# Vertigo_Core.net
KiCad netlist of a schematic drawn in Altium Designer
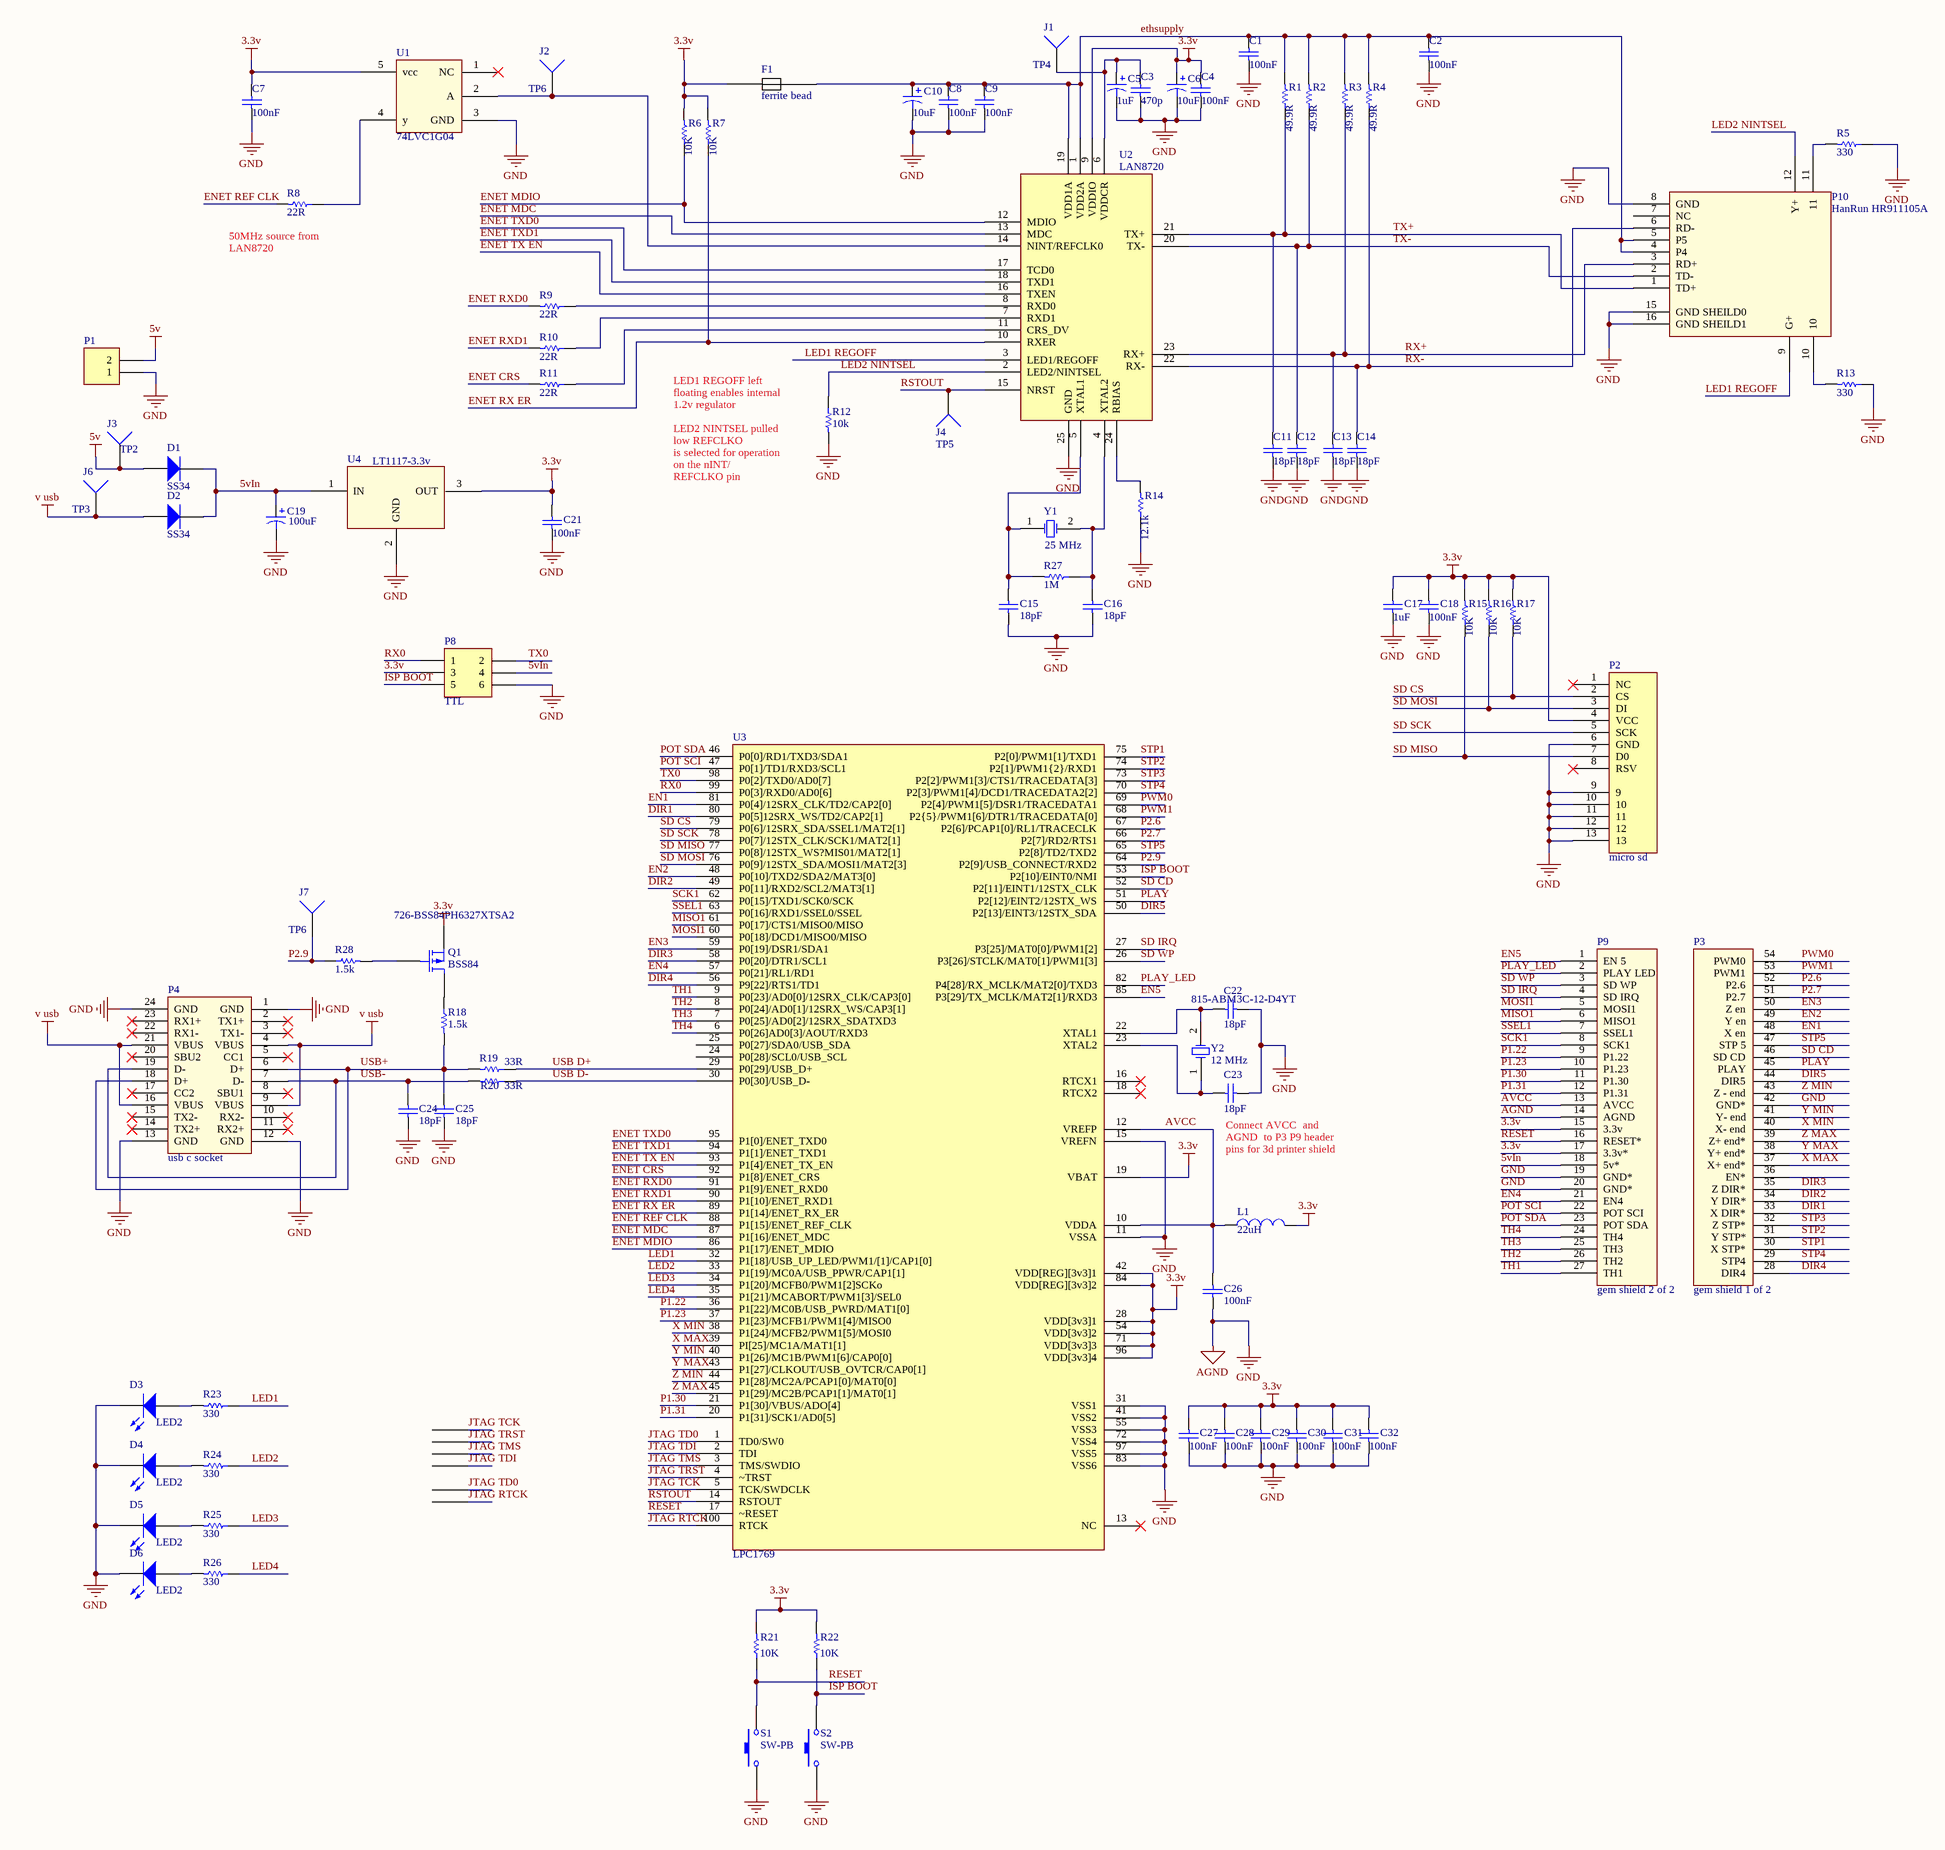
[diagram p0: Vertigo Core.SchDoc]

(export (version "E")
  (design (tool "Eeschema 10.0.6"))
  (components
    (comp (ref "C1")
      (value "100nF")
      (footprint "0805")
      (description "Capacitor (Semiconductor SIM Model)")
      (fields (field (name "PUBLISHER") "Altium Limited"))
      (libsource (lib "Miscellaneous Devices") (part "Cap Semi"))
    )
    (comp (ref "C2")
      (value "100nF")
      (footprint "0805")
      (description "Capacitor (Semiconductor SIM Model)")
      (fields (field (name "PUBLISHER") "Altium Limited"))
      (libsource (lib "Miscellaneous Devices") (part "Cap Semi"))
    )
    (comp (ref "C3")
      (value "470p")
      (footprint "0805")
      (description "Capacitor (Semiconductor SIM Model)")
      (fields (field (name "Comment") "470pF") (field (name "PUBLISHER") "Altium Limited"))
      (libsource (lib "Miscellaneous Devices") (part "Cap Semi"))
    )
    (comp (ref "C4")
      (value "100nF")
      (footprint "0805")
      (description "Capacitor (Semiconductor SIM Model)")
      (fields (field (name "PUBLISHER") "Altium Limited"))
      (libsource (lib "Miscellaneous Devices") (part "Cap Semi"))
    )
    (comp (ref "C5")
      (value "1uF")
      (footprint "0805")
      (description "Polarized Capacitor (Radial)")
      (fields (field (name "PUBLISHER") "Altium Limited"))
      (libsource (lib "Miscellaneous Devices") (part "Cap Pol1"))
    )
    (comp (ref "C6")
      (value "10uF")
      (footprint "0805")
      (description "Polarized Capacitor (Radial)")
      (fields (field (name "PUBLISHER") "Altium Limited"))
      (libsource (lib "Miscellaneous Devices") (part "Cap Pol1"))
    )
    (comp (ref "C7")
      (value "100nF")
      (footprint "0805")
      (description "Capacitor (Semiconductor SIM Model)")
      (fields (field (name "PUBLISHER") "Altium Limited"))
      (libsource (lib "Miscellaneous Devices") (part "Cap Semi"))
    )
    (comp (ref "C8")
      (value "100nF")
      (footprint "0805")
      (description "Capacitor (Semiconductor SIM Model)")
      (fields (field (name "PUBLISHER") "Altium Limited"))
      (libsource (lib "Miscellaneous Devices") (part "Cap Semi"))
    )
    (comp (ref "C9")
      (value "100nF")
      (footprint "0805")
      (description "Capacitor (Semiconductor SIM Model)")
      (fields (field (name "PUBLISHER") "Altium Limited"))
      (libsource (lib "Miscellaneous Devices") (part "Cap Semi"))
    )
    (comp (ref "C10")
      (value "10uF")
      (footprint "0805")
      (description "Polarized Capacitor (Radial)")
      (fields (field (name "PUBLISHER") "Altium Limited"))
      (libsource (lib "Miscellaneous Devices") (part "Cap Pol1"))
    )
    (comp (ref "C11")
      (value "18pF")
      (footprint "0805")
      (description "Capacitor (Semiconductor SIM Model)")
      (fields (field (name "Comment") "18pf") (field (name "PUBLISHER") "Altium Limited"))
      (libsource (lib "Miscellaneous Devices") (part "Cap Semi"))
    )
    (comp (ref "C12")
      (value "18pF")
      (footprint "0805")
      (description "Capacitor (Semiconductor SIM Model)")
      (fields (field (name "Comment") "18pf") (field (name "PUBLISHER") "Altium Limited"))
      (libsource (lib "Miscellaneous Devices") (part "Cap Semi"))
    )
    (comp (ref "C13")
      (value "18pF")
      (footprint "0805")
      (description "Capacitor (Semiconductor SIM Model)")
      (fields (field (name "Comment") "18pf") (field (name "PUBLISHER") "Altium Limited"))
      (libsource (lib "Miscellaneous Devices") (part "Cap Semi"))
    )
    (comp (ref "C14")
      (value "18pF")
      (footprint "0805")
      (description "Capacitor (Semiconductor SIM Model)")
      (fields (field (name "Comment") "18pf") (field (name "PUBLISHER") "Altium Limited"))
      (libsource (lib "Miscellaneous Devices") (part "Cap Semi"))
    )
    (comp (ref "C15")
      (value "18pF")
      (footprint "0805")
      (description "Capacitor (Semiconductor SIM Model)")
      (fields (field (name "PUBLISHER") "Altium Limited"))
      (libsource (lib "Miscellaneous Devices") (part "Cap Semi"))
    )
    (comp (ref "C16")
      (value "18pF")
      (footprint "0805")
      (description "Capacitor (Semiconductor SIM Model)")
      (fields (field (name "PUBLISHER") "Altium Limited"))
      (libsource (lib "Miscellaneous Devices") (part "Cap Semi"))
    )
    (comp (ref "C17")
      (value "1uF")
      (footprint "0805")
      (description "Capacitor (Semiconductor SIM Model)")
      (fields (field (name "PUBLISHER") "Altium Limited"))
      (libsource (lib "Miscellaneous Devices") (part "Cap Semi"))
    )
    (comp (ref "C18")
      (value "100nF")
      (footprint "0805")
      (description "Capacitor (Semiconductor SIM Model)")
      (fields (field (name "PUBLISHER") "Altium Limited"))
      (libsource (lib "Miscellaneous Devices") (part "Cap Semi"))
    )
    (comp (ref "C19")
      (value "100uF")
      (footprint "470uf/ 100uf 50v smd")
      (description "Polarized Capacitor (Radial)")
      (fields (field (name "Comment") "10uF") (field (name "PUBLISHER") "Altium Limited"))
      (libsource (lib "Miscellaneous Devices") (part "Cap Pol1"))
    )
    (comp (ref "C21")
      (value "100nF")
      (footprint "0805")
      (description "Capacitor (Semiconductor SIM Model)")
      (fields (field (name "PUBLISHER") "Altium Limited"))
      (libsource (lib "Miscellaneous Devices") (part "Cap Semi"))
    )
    (comp (ref "C22")
      (value "18pF")
      (footprint "0805")
      (description "Capacitor (Semiconductor SIM Model)")
      (fields (field (name "PUBLISHER") "Altium Limited"))
      (libsource (lib "Miscellaneous Devices") (part "Cap Semi"))
    )
    (comp (ref "C23")
      (value "18pF")
      (footprint "0805")
      (description "Capacitor (Semiconductor SIM Model)")
      (fields (field (name "PUBLISHER") "Altium Limited"))
      (libsource (lib "Miscellaneous Devices") (part "Cap Semi"))
    )
    (comp (ref "C24")
      (value "18pF")
      (footprint "0805")
      (description "Capacitor (Semiconductor SIM Model)")
      (fields (field (name "PUBLISHER") "Altium Limited"))
      (libsource (lib "Miscellaneous Devices") (part "Cap Semi"))
    )
    (comp (ref "C25")
      (value "18pF")
      (footprint "0805")
      (description "Capacitor (Semiconductor SIM Model)")
      (fields (field (name "PUBLISHER") "Altium Limited"))
      (libsource (lib "Miscellaneous Devices") (part "Cap Semi"))
    )
    (comp (ref "C26")
      (value "100nF")
      (footprint "0805")
      (description "Capacitor (Semiconductor SIM Model)")
      (fields (field (name "PUBLISHER") "Altium Limited"))
      (libsource (lib "Miscellaneous Devices") (part "Cap Semi"))
    )
    (comp (ref "C27")
      (value "100nF")
      (footprint "0805")
      (description "Capacitor (Semiconductor SIM Model)")
      (fields (field (name "PUBLISHER") "Altium Limited"))
      (libsource (lib "Miscellaneous Devices") (part "Cap Semi"))
    )
    (comp (ref "C28")
      (value "100nF")
      (footprint "0805")
      (description "Capacitor (Semiconductor SIM Model)")
      (fields (field (name "PUBLISHER") "Altium Limited"))
      (libsource (lib "Miscellaneous Devices") (part "Cap Semi"))
    )
    (comp (ref "C29")
      (value "100nF")
      (footprint "0805")
      (description "Capacitor (Semiconductor SIM Model)")
      (fields (field (name "PUBLISHER") "Altium Limited"))
      (libsource (lib "Miscellaneous Devices") (part "Cap Semi"))
    )
    (comp (ref "C30")
      (value "100nF")
      (footprint "0805")
      (description "Capacitor (Semiconductor SIM Model)")
      (fields (field (name "PUBLISHER") "Altium Limited"))
      (libsource (lib "Miscellaneous Devices") (part "Cap Semi"))
    )
    (comp (ref "C31")
      (value "100nF")
      (footprint "0805")
      (description "Capacitor (Semiconductor SIM Model)")
      (fields (field (name "PUBLISHER") "Altium Limited"))
      (libsource (lib "Miscellaneous Devices") (part "Cap Semi"))
    )
    (comp (ref "C32")
      (value "100nF")
      (footprint "0805")
      (description "Capacitor (Semiconductor SIM Model)")
      (fields (field (name "PUBLISHER") "Altium Limited"))
      (libsource (lib "Miscellaneous Devices") (part "Cap Semi"))
    )
    (comp (ref "D1")
      (value "SS34")
      (footprint "Diode")
      (description "High Conductance Fast Diode")
      (fields (field (name "PUBLISHER") "Altium Limited"))
      (libsource (lib "Miscellaneous Devices") (part "Diode 1N914"))
    )
    (comp (ref "D2")
      (value "SS34")
      (footprint "Diode")
      (description "High Conductance Fast Diode")
      (fields (field (name "PUBLISHER") "Altium Limited"))
      (libsource (lib "Miscellaneous Devices") (part "Diode 1N914"))
    )
    (comp (ref "D3")
      (value "LED2")
      (footprint "0805 LED")
      (description "Typical RED, GREEN, YELLOW, AMBER GaAs LED")
      (fields (field (name "PUBLISHER") "Altium Limited"))
      (libsource (lib "Miscellaneous Devices") (part "LED2"))
    )
    (comp (ref "D4")
      (value "LED2")
      (footprint "0805 LED")
      (description "Typical RED, GREEN, YELLOW, AMBER GaAs LED")
      (fields (field (name "PUBLISHER") "Altium Limited"))
      (libsource (lib "Miscellaneous Devices") (part "LED2"))
    )
    (comp (ref "D5")
      (value "LED2")
      (footprint "0805 LED")
      (description "Typical RED, GREEN, YELLOW, AMBER GaAs LED")
      (fields (field (name "PUBLISHER") "Altium Limited"))
      (libsource (lib "Miscellaneous Devices") (part "LED2"))
    )
    (comp (ref "D6")
      (value "LED2")
      (footprint "0805 LED")
      (description "Typical RED, GREEN, YELLOW, AMBER GaAs LED")
      (fields (field (name "PUBLISHER") "Altium Limited"))
      (libsource (lib "Miscellaneous Devices") (part "LED2"))
    )
    (comp (ref "F1")
      (value "ferrite bead")
      (footprint "0805")
      (libsource (lib "32 bit cnc") (part "ferrite bead"))
    )
    (comp (ref "J1")
      (value "TP4")
      (footprint "test point")
      (description "Socket")
      (fields (field (name "PUBLISHER") "Altium Limited"))
      (libsource (lib "Miscellaneous Connectors") (part "Socket"))
    )
    (comp (ref "J2")
      (value "TP6")
      (footprint "test point")
      (description "Socket")
      (fields (field (name "PUBLISHER") "Altium Limited"))
      (libsource (lib "Miscellaneous Connectors") (part "Socket"))
    )
    (comp (ref "J3")
      (value "TP2")
      (footprint "test point")
      (description "Socket")
      (fields (field (name "PUBLISHER") "Altium Limited"))
      (libsource (lib "Miscellaneous Connectors") (part "Socket"))
    )
    (comp (ref "J4")
      (value "TP5")
      (footprint "test point")
      (description "Socket")
      (fields (field (name "PUBLISHER") "Altium Limited"))
      (libsource (lib "Miscellaneous Connectors") (part "Socket"))
    )
    (comp (ref "J6")
      (value "TP3")
      (footprint "test point")
      (description "Socket")
      (fields (field (name "PUBLISHER") "Altium Limited"))
      (libsource (lib "Miscellaneous Connectors") (part "Socket"))
    )
    (comp (ref "J7")
      (value "TP6")
      (footprint "test point")
      (description "Socket")
      (fields (field (name "PUBLISHER") "Altium Limited"))
      (libsource (lib "Miscellaneous Connectors") (part "Socket"))
    )
    (comp (ref "L1")
      (value "22uH")
      (footprint "0805")
      (description "Inductor")
      (fields (field (name "PUBLISHER") "Altium Limited"))
      (libsource (lib "Miscellaneous Devices") (part "Inductor"))
    )
    (comp (ref "P1")
      (value "Header 2")
      (footprint "HDR1X2")
      (description "Header, 2-Pin")
      (fields (field (name "PUBLISHER") "Altium Limited"))
      (libsource (lib "Miscellaneous Connectors") (part "Header 2"))
    )
    (comp (ref "P2")
      (value "micro sd")
      (footprint "DM3 SD card")
      (libsource (lib "32 bit cnc") (part "micro sd"))
    )
    (comp (ref "P3")
      (value "gem shield 1 of 2")
      (footprint "gem shield 1 of 2")
      (libsource (lib "32 bit cnc") (part "gem shield 1 of 2"))
    )
    (comp (ref "P4")
      (value "usb c socket")
      (footprint "USB C type")
      (description "Mouser 538-105450-0101")
      (libsource (lib "32 bit cnc") (part "usb c socket"))
    )
    (comp (ref "P5") (value "JTAG2") (footprint "JTAG2") (libsource (lib "32 bit cnc") (part "JTAG2")))
    (comp (ref "P6") (value "JTAG") (footprint "JTAG") (libsource (lib "32 bit cnc") (part "JTAG")))
    (comp (ref "P8")
      (value "TTL")
      (footprint "HDR2X3")
      (description "Header, 3-Pin, Dual row")
      (fields (field (name "PUBLISHER") "Altium Limited"))
      (libsource (lib "Miscellaneous Connectors") (part "Header 3X2"))
    )
    (comp (ref "P9")
      (value "gem shield 2 of 2")
      (footprint "gem shield 2 of 2")
      (libsource (lib "32 bit cnc") (part "gem shield 2 of 2"))
    )
    (comp (ref "P10")
      (value "HanRun HR911105A")
      (footprint "Hanrun")
      (libsource (lib "32 bit cnc") (part "RJ45"))
    )
    (comp (ref "Q1")
      (value "BSS84")
      (footprint "SOT23")
      (description "P-Channel MOSFET")
      (fields
        (field (name "SUPPLIER PART NUMBER 1") "726-BSS84PH6327XTSA2")
        (field (name "PUBLISHER") "Altium Limited")
      )
      (libsource (lib "Miscellaneous Devices") (part "MOSFET-P"))
    )
    (comp (ref "R1")
      (value "49.9R")
      (footprint "0805")
      (description "Resistor")
      (fields (field (name "Comment") "49.9") (field (name "PUBLISHER") "Altium Limited"))
      (libsource (lib "Miscellaneous Devices") (part "Res1"))
    )
    (comp (ref "R2")
      (value "49.9R")
      (footprint "0805")
      (description "Resistor")
      (fields (field (name "Comment") "49.9") (field (name "PUBLISHER") "Altium Limited"))
      (libsource (lib "Miscellaneous Devices") (part "Res1"))
    )
    (comp (ref "R3")
      (value "49.9R")
      (footprint "0805")
      (description "Resistor")
      (fields (field (name "Comment") "49.9") (field (name "PUBLISHER") "Altium Limited"))
      (libsource (lib "Miscellaneous Devices") (part "Res1"))
    )
    (comp (ref "R4")
      (value "49.9R")
      (footprint "0805")
      (description "Resistor")
      (fields (field (name "Comment") "49.9") (field (name "PUBLISHER") "Altium Limited"))
      (libsource (lib "Miscellaneous Devices") (part "Res1"))
    )
    (comp (ref "R5")
      (value "330")
      (footprint "0805")
      (description "Resistor")
      (fields (field (name "PUBLISHER") "Altium Limited"))
      (libsource (lib "Miscellaneous Devices") (part "Res1"))
    )
    (comp (ref "R6")
      (value "10K")
      (footprint "0805")
      (description "Resistor")
      (fields (field (name "Comment") "10k") (field (name "PUBLISHER") "Altium Limited"))
      (libsource (lib "Miscellaneous Devices") (part "Res1"))
    )
    (comp (ref "R7")
      (value "10K")
      (footprint "0805")
      (description "Resistor")
      (fields (field (name "Comment") "10k") (field (name "PUBLISHER") "Altium Limited"))
      (libsource (lib "Miscellaneous Devices") (part "Res1"))
    )
    (comp (ref "R8")
      (value "22R")
      (footprint "0603")
      (description "Resistor")
      (fields (field (name "PUBLISHER") "Altium Limited"))
      (libsource (lib "Miscellaneous Devices") (part "Res1"))
    )
    (comp (ref "R9")
      (value "22R")
      (footprint "0603")
      (description "Resistor")
      (fields (field (name "PUBLISHER") "Altium Limited"))
      (libsource (lib "Miscellaneous Devices") (part "Res1"))
    )
    (comp (ref "R10")
      (value "22R")
      (footprint "0603")
      (description "Resistor")
      (fields (field (name "PUBLISHER") "Altium Limited"))
      (libsource (lib "Miscellaneous Devices") (part "Res1"))
    )
    (comp (ref "R11")
      (value "22R")
      (footprint "0603")
      (description "Resistor")
      (fields (field (name "PUBLISHER") "Altium Limited"))
      (libsource (lib "Miscellaneous Devices") (part "Res1"))
    )
    (comp (ref "R12")
      (value "10k")
      (footprint "0805")
      (description "Resistor")
      (fields (field (name "PUBLISHER") "Altium Limited"))
      (libsource (lib "Miscellaneous Devices") (part "Res1"))
    )
    (comp (ref "R13")
      (value "330")
      (footprint "0805")
      (description "Resistor")
      (fields (field (name "PUBLISHER") "Altium Limited"))
      (libsource (lib "Miscellaneous Devices") (part "Res1"))
    )
    (comp (ref "R14")
      (value "12.1k")
      (footprint "0805")
      (description "Resistor")
      (fields (field (name "PUBLISHER") "Altium Limited"))
      (libsource (lib "Miscellaneous Devices") (part "Res1"))
    )
    (comp (ref "R15")
      (value "10K")
      (footprint "0805")
      (description "Resistor")
      (fields (field (name "Comment") "10k") (field (name "PUBLISHER") "Altium Limited"))
      (libsource (lib "Miscellaneous Devices") (part "Res1"))
    )
    (comp (ref "R16")
      (value "10K")
      (footprint "0805")
      (description "Resistor")
      (fields (field (name "Comment") "10k") (field (name "PUBLISHER") "Altium Limited"))
      (libsource (lib "Miscellaneous Devices") (part "Res1"))
    )
    (comp (ref "R17")
      (value "10K")
      (footprint "0805")
      (description "Resistor")
      (fields (field (name "Comment") "10k") (field (name "PUBLISHER") "Altium Limited"))
      (libsource (lib "Miscellaneous Devices") (part "Res1"))
    )
    (comp (ref "R18")
      (value "1.5k")
      (footprint "0603")
      (description "Resistor")
      (fields (field (name "Comment") "1.5K") (field (name "PUBLISHER") "Altium Limited"))
      (libsource (lib "Miscellaneous Devices") (part "Res1"))
    )
    (comp (ref "R19")
      (value "33R")
      (footprint "0805")
      (description "Resistor")
      (fields (field (name "PUBLISHER") "Altium Limited"))
      (libsource (lib "Miscellaneous Devices") (part "Res1"))
    )
    (comp (ref "R20")
      (value "33R")
      (footprint "0805")
      (description "Resistor")
      (fields (field (name "PUBLISHER") "Altium Limited"))
      (libsource (lib "Miscellaneous Devices") (part "Res1"))
    )
    (comp (ref "R21")
      (value "10K")
      (footprint "0805")
      (description "Resistor")
      (fields (field (name "Comment") "10k") (field (name "PUBLISHER") "Altium Limited"))
      (libsource (lib "Miscellaneous Devices") (part "Res1"))
    )
    (comp (ref "R22")
      (value "10K")
      (footprint "0805")
      (description "Resistor")
      (fields (field (name "Comment") "10k") (field (name "PUBLISHER") "Altium Limited"))
      (libsource (lib "Miscellaneous Devices") (part "Res1"))
    )
    (comp (ref "R23")
      (value "330")
      (footprint "0805")
      (description "Resistor")
      (fields (field (name "PUBLISHER") "Altium Limited"))
      (libsource (lib "Miscellaneous Devices") (part "Res1"))
    )
    (comp (ref "R24")
      (value "330")
      (footprint "0805")
      (description "Resistor")
      (fields (field (name "PUBLISHER") "Altium Limited"))
      (libsource (lib "Miscellaneous Devices") (part "Res1"))
    )
    (comp (ref "R25")
      (value "330")
      (footprint "0805")
      (description "Resistor")
      (fields (field (name "PUBLISHER") "Altium Limited"))
      (libsource (lib "Miscellaneous Devices") (part "Res1"))
    )
    (comp (ref "R26")
      (value "330")
      (footprint "0805")
      (description "Resistor")
      (fields (field (name "PUBLISHER") "Altium Limited"))
      (libsource (lib "Miscellaneous Devices") (part "Res1"))
    )
    (comp (ref "R27")
      (value "1M")
      (footprint "0805")
      (description "Resistor")
      (fields (field (name "PUBLISHER") "Altium Limited"))
      (libsource (lib "Miscellaneous Devices") (part "Res1"))
    )
    (comp (ref "R28")
      (value "1.5k")
      (footprint "0603")
      (description "Resistor")
      (fields (field (name "Comment") "1.5K") (field (name "PUBLISHER") "Altium Limited"))
      (libsource (lib "Miscellaneous Devices") (part "Res1"))
    )
    (comp (ref "S1")
      (value "SW-PB")
      (footprint "SMD_push_button")
      (description "Switch")
      (fields (field (name "PUBLISHER") "Altium Limited"))
      (libsource (lib "Miscellaneous Devices") (part "SW-PB"))
    )
    (comp (ref "S2")
      (value "SW-PB")
      (footprint "SMD_push_button")
      (description "Switch")
      (fields (field (name "PUBLISHER") "Altium Limited"))
      (libsource (lib "Miscellaneous Devices") (part "SW-PB"))
    )
    (comp (ref "U1")
      (value "74LVC1G04")
      (footprint "SOT23-5")
      (libsource (lib "32 bit cnc") (part "74LVC1G04"))
    )
    (comp (ref "U2")
      (value "LAN8720")
      (footprint "QFN50P400X400X100-24N")
      (libsource (lib "32 bit cnc") (part "LAN8720"))
    )
    (comp (ref "U3")
      (value "LPC1769")
      (footprint "TSQFP50P1600X1600X160_HS-101N")
      (libsource (lib "32 bit cnc") (part "LPC1769"))
    )
    (comp (ref "U4")
      (value "LT1117-3.3v")
      (footprint "SOT223")
      (libsource (lib "32 bit cnc") (part "LT1117-3.3v"))
    )
    (comp (ref "Y1")
      (value "25 MHz")
      (footprint "25 MHz crystal M445")
      (description "Crystal Oscillator")
      (fields (field (name "PUBLISHER") "Altium Limited"))
      (libsource (lib "Miscellaneous Devices") (part "XTAL"))
    )
    (comp (ref "Y2")
      (value "12 MHz")
      (footprint "SMD_crystal")
      (description "Crystal Oscillator")
      (fields
        (field (name "SUPPLIER PART NUMBER 4") "815-ABM3C-12-D4YT")
        (field (name "PUBLISHER") "Altium Limited")
      )
      (libsource (lib "Miscellaneous Devices") (part "XTAL"))
    )
  )
  (nets
    (net (code "1") (name "/5vIn") (class "Default")
      (node (ref "C19") (pin "1") (pinfunction "1_1") (pintype "passive"))
      (node (ref "D1") (pin "2") (pinfunction "K_2") (pintype "passive"))
      (node (ref "D2") (pin "2") (pinfunction "K_2") (pintype "passive"))
      (node (ref "P8") (pin "4") (pinfunction "4_4") (pintype "passive"))
      (node (ref "P9") (pin "18") (pinfunction "5v*_18") (pintype "passive"))
      (node (ref "U4") (pin "1") (pinfunction "IN_1") (pintype "passive"))
    )
    (net (code "2") (name "/AVCC") (class "Default")
      (node (ref "C26") (pin "1") (pinfunction "1_1") (pintype "passive"))
      (node (ref "L1") (pin "1") (pinfunction "1_1") (pintype "passive"))
      (node (ref "P9") (pin "13") (pinfunction "AVCC_13") (pintype "passive"))
      (node (ref "U3") (pin "10") (pinfunction "VDDA_10") (pintype "passive"))
      (node (ref "U3") (pin "12") (pinfunction "VREFP_12") (pintype "passive"))
    )
    (net (code "3") (name "/DIR1") (class "Default")
      (node (ref "P3") (pin "33") (pinfunction "X_DIR*_33") (pintype "passive"))
      (node (ref "U3") (pin "80") (pinfunction "P0[5]12SRX_WS/TD2/CAP2[1]_80") (pintype "passive"))
    )
    (net (code "4") (name "/DIR2") (class "Default")
      (node (ref "P3") (pin "34") (pinfunction "Y_DIR*_34") (pintype "passive"))
      (node (ref "U3") (pin "49") (pinfunction "P0[11]/RXD2/SCL2/MAT3[1]_49") (pintype "passive"))
    )
    (net (code "5") (name "/DIR3") (class "Default")
      (node (ref "P3") (pin "35") (pinfunction "Z_DIR*_35") (pintype "passive"))
      (node (ref "U3") (pin "58") (pinfunction "P0[20]/DTR1/SCL1_58") (pintype "passive"))
    )
    (net (code "6") (name "/DIR4") (class "Default")
      (node (ref "P3") (pin "28") (pinfunction "DIR4_28") (pintype "passive"))
      (node (ref "U3") (pin "56") (pinfunction "P9[22]/RTS1/TD1_56") (pintype "passive"))
    )
    (net (code "7") (name "/DIR5") (class "Default")
      (node (ref "P3") (pin "44") (pinfunction "DIR5_44") (pintype "passive"))
      (node (ref "U3") (pin "50") (pinfunction "P2[13]/EINT3/12STX_SDA_50") (pintype "passive"))
    )
    (net (code "8") (name "/EN1") (class "Default")
      (node (ref "P3") (pin "48") (pinfunction "X_en_48") (pintype "passive"))
      (node (ref "U3") (pin "81") (pinfunction "P0[4]/12SRX_CLK/TD2/CAP2[0]_81") (pintype "passive"))
    )
    (net (code "9") (name "/EN2") (class "Default")
      (node (ref "P3") (pin "49") (pinfunction "Y_en_49") (pintype "passive"))
      (node (ref "U3") (pin "48") (pinfunction "P0[10]/TXD2/SDA2/MAT3[0]_48") (pintype "passive"))
    )
    (net (code "10") (name "/EN3") (class "Default")
      (node (ref "P3") (pin "50") (pinfunction "Z_en_50") (pintype "passive"))
      (node (ref "U3") (pin "59") (pinfunction "P0[19]/DSR1/SDA1_59") (pintype "passive"))
    )
    (net (code "11") (name "/EN4") (class "Default")
      (node (ref "P9") (pin "21") (pinfunction "EN4_21") (pintype "passive"))
      (node (ref "U3") (pin "57") (pinfunction "P0[21]/RL1/RD1_57") (pintype "passive"))
    )
    (net (code "12") (name "/EN5") (class "Default")
      (node (ref "P9") (pin "1") (pinfunction "EN_5_1") (pintype "passive"))
      (node (ref "U3") (pin "85") (pinfunction "P3[29]/TX_MCLK/MAT2[1]/RXD3_85") (pintype "passive"))
    )
    (net (code "13") (name "/ENET CRS") (class "Default")
      (node (ref "R11") (pin "2") (pinfunction "2_2") (pintype "passive"))
      (node (ref "U3") (pin "92") (pinfunction "P1[8]/ENET_CRS_92") (pintype "passive"))
    )
    (net (code "14") (name "/ENET MDC") (class "Default")
      (node (ref "U2") (pin "13") (pinfunction "MDC_13") (pintype "passive"))
      (node (ref "U3") (pin "87") (pinfunction "P1[16]/ENET_MDC_87") (pintype "passive"))
    )
    (net (code "15") (name "/ENET MDIO") (class "Default")
      (node (ref "R6") (pin "1") (pinfunction "1_1") (pintype "passive"))
      (node (ref "U2") (pin "12") (pinfunction "MDIO_12") (pintype "passive"))
      (node (ref "U3") (pin "86") (pinfunction "P1[17]/ENET_MDIO_86") (pintype "passive"))
    )
    (net (code "16") (name "/ENET REF CLK") (class "Default")
      (node (ref "R8") (pin "2") (pinfunction "2_2") (pintype "passive"))
      (node (ref "U3") (pin "88") (pinfunction "P1[15]/ENET_REF_CLK_88") (pintype "passive"))
    )
    (net (code "17") (name "/ENET RX ER") (class "Default")
      (node (ref "R7") (pin "1") (pinfunction "1_1") (pintype "passive"))
      (node (ref "U2") (pin "10") (pinfunction "RXER_10") (pintype "passive"))
      (node (ref "U3") (pin "89") (pinfunction "P1[14]/ENET_RX_ER_89") (pintype "passive"))
    )
    (net (code "18") (name "/ENET RXD0") (class "Default")
      (node (ref "R9") (pin "2") (pinfunction "2_2") (pintype "passive"))
      (node (ref "U3") (pin "91") (pinfunction "P1[9]/ENET_RXD0_91") (pintype "passive"))
    )
    (net (code "19") (name "/ENET RXD1") (class "Default")
      (node (ref "R10") (pin "2") (pinfunction "2_2") (pintype "passive"))
      (node (ref "U3") (pin "90") (pinfunction "P1[10]/ENET_RXD1_90") (pintype "passive"))
    )
    (net (code "20") (name "/ENET TX EN") (class "Default")
      (node (ref "U2") (pin "16") (pinfunction "TXEN_16") (pintype "passive"))
      (node (ref "U3") (pin "93") (pinfunction "P1[4]/ENET_TX_EN_93") (pintype "passive"))
    )
    (net (code "21") (name "/ENET TXD0") (class "Default")
      (node (ref "U2") (pin "17") (pinfunction "TCD0_17") (pintype "passive"))
      (node (ref "U3") (pin "95") (pinfunction "P1[0]/ENET_TXD0_95") (pintype "passive"))
    )
    (net (code "22") (name "/ENET TXD1") (class "Default")
      (node (ref "U2") (pin "18") (pinfunction "TXD1_18") (pintype "passive"))
      (node (ref "U3") (pin "94") (pinfunction "P1[1]/ENET_TXD1_94") (pintype "passive"))
    )
    (net (code "23") (name "/ISP BOOT") (class "Default")
      (node (ref "P8") (pin "5") (pinfunction "5_5") (pintype "passive"))
      (node (ref "R22") (pin "1") (pinfunction "1_1") (pintype "passive"))
      (node (ref "S2") (pin "2") (pinfunction "2_2") (pintype "passive"))
      (node (ref "U3") (pin "53") (pinfunction "P2[10]/EINT0/NMI_53") (pintype "passive"))
    )
    (net (code "24") (name "/JTAG RTCK") (class "Default")
      (node (ref "P5") (pin "1") (pinfunction "1_1") (pintype "passive"))
      (node (ref "U3") (pin "100") (pinfunction "RTCK_100") (pintype "passive"))
    )
    (net (code "25") (name "/JTAG TCK") (class "Default")
      (node (ref "P6") (pin "4") (pinfunction "4_4") (pintype "passive"))
      (node (ref "U3") (pin "5") (pinfunction "TCK/SWDCLK_5") (pintype "passive"))
    )
    (net (code "26") (name "/JTAG TD0") (class "Default")
      (node (ref "P5") (pin "2") (pinfunction "2_2") (pintype "passive"))
      (node (ref "U3") (pin "1") (pinfunction "TD0/SW0_1") (pintype "passive"))
    )
    (net (code "27") (name "/JTAG TDI") (class "Default")
      (node (ref "P6") (pin "1") (pinfunction "1_1") (pintype "passive"))
      (node (ref "U3") (pin "2") (pinfunction "TDI_2") (pintype "passive"))
    )
    (net (code "28") (name "/JTAG TMS") (class "Default")
      (node (ref "P6") (pin "2") (pinfunction "2_2") (pintype "passive"))
      (node (ref "U3") (pin "3") (pinfunction "TMS/SWDIO_3") (pintype "passive"))
    )
    (net (code "29") (name "/JTAG TRST") (class "Default")
      (node (ref "P6") (pin "3") (pinfunction "3_3") (pintype "passive"))
      (node (ref "U3") (pin "4") (pinfunction "~TRST_4") (pintype "passive"))
    )
    (net (code "30") (name "/LED1") (class "Default")
      (node (ref "R23") (pin "1") (pinfunction "1_1") (pintype "passive"))
      (node (ref "U3") (pin "32") (pinfunction "P1[18]/USB_UP_LED/PWM1/[1]/CAP1[0]_32") (pintype "passive"))
    )
    (net (code "31") (name "/LED1 REGOFF") (class "Default")
      (node (ref "P10") (pin "9") (pinfunction "G+_9") (pintype "passive"))
      (node (ref "U2") (pin "3") (pinfunction "LED1/REGOFF_3") (pintype "passive"))
    )
    (net (code "32") (name "/LED2") (class "Default")
      (node (ref "R24") (pin "1") (pinfunction "1_1") (pintype "passive"))
      (node (ref "U3") (pin "33") (pinfunction "P1[19]/MC0A/USB_PPWR/CAP1[1]_33") (pintype "passive"))
    )
    (net (code "33") (name "/LED2 NINTSEL") (class "Default")
      (node (ref "P10") (pin "12") (pinfunction "Y+_12") (pintype "passive"))
      (node (ref "R12") (pin "1") (pinfunction "1_1") (pintype "passive"))
      (node (ref "U2") (pin "2") (pinfunction "LED2/NINTSEL_2") (pintype "passive"))
    )
    (net (code "34") (name "/LED3") (class "Default")
      (node (ref "R25") (pin "1") (pinfunction "1_1") (pintype "passive"))
      (node (ref "U3") (pin "34") (pinfunction "P1[20]/MCFB0/PWM1[2]SCKo_34") (pintype "passive"))
    )
    (net (code "35") (name "/LED4") (class "Default")
      (node (ref "R26") (pin "1") (pinfunction "1_1") (pintype "passive"))
      (node (ref "U3") (pin "35") (pinfunction "P1[21]/MCABORT/PWM1[3]/SEL0_35") (pintype "passive"))
    )
    (net (code "36") (name "/MISO1") (class "Default")
      (node (ref "P9") (pin "6") (pinfunction "MISO1_6") (pintype "passive"))
      (node (ref "U3") (pin "61") (pinfunction "P0[17]/CTS1/MISO0/MISO_61") (pintype "passive"))
    )
    (net (code "37") (name "/MOSI1") (class "Default")
      (node (ref "P9") (pin "5") (pinfunction "MOSI1_5") (pintype "passive"))
      (node (ref "U3") (pin "60") (pinfunction "P0[18]/DCD1/MISO0/MISO_60") (pintype "passive"))
    )
    (net (code "38") (name "/P1.22") (class "Default")
      (node (ref "P9") (pin "9") (pinfunction "P1.22_9") (pintype "passive"))
      (node (ref "U3") (pin "36") (pinfunction "P1[22]/MC0B/USB_PWRD/MAT1[0]_36") (pintype "passive"))
    )
    (net (code "39") (name "/P1.23") (class "Default")
      (node (ref "P9") (pin "10") (pinfunction "P1.23_10") (pintype "passive"))
      (node (ref "U3") (pin "37") (pinfunction "P1[23]/MCFB1/PWM1[4]/MISO0_37") (pintype "passive"))
    )
    (net (code "40") (name "/P1.30") (class "Default")
      (node (ref "P9") (pin "11") (pinfunction "P1.30_11") (pintype "passive"))
      (node (ref "U3") (pin "21") (pinfunction "P1[30]/VBUS/ADO[4]_21") (pintype "passive"))
    )
    (net (code "41") (name "/P1.31") (class "Default")
      (node (ref "P9") (pin "12") (pinfunction "P1.31_12") (pintype "passive"))
      (node (ref "U3") (pin "20") (pinfunction "P1[31]/SCK1/AD0[5]_20") (pintype "passive"))
    )
    (net (code "42") (name "/P2.6") (class "Default")
      (node (ref "P3") (pin "52") (pinfunction "P2.6_52") (pintype "passive"))
      (node (ref "U3") (pin "67") (pinfunction "P2[6]/PCAP1[0]/RL1/TRACECLK_67") (pintype "passive"))
    )
    (net (code "43") (name "/P2.7") (class "Default")
      (node (ref "P3") (pin "51") (pinfunction "P2.7_51") (pintype "passive"))
      (node (ref "U3") (pin "66") (pinfunction "P2[7]/RD2/RTS1_66") (pintype "passive"))
    )
    (net (code "44") (name "/P2.9") (class "Default")
      (node (ref "J7") (pin "1") (pinfunction "1_1") (pintype "passive"))
      (node (ref "R28") (pin "1") (pinfunction "1_1") (pintype "passive"))
      (node (ref "U3") (pin "64") (pinfunction "P2[9]/USB_CONNECT/RXD2_64") (pintype "passive"))
    )
    (net (code "45") (name "/PLAY") (class "Default")
      (node (ref "P3") (pin "45") (pinfunction "PLAY_45") (pintype "passive"))
      (node (ref "U3") (pin "51") (pinfunction "P2[12]/EINT2/12STX_WS_51") (pintype "passive"))
    )
    (net (code "46") (name "/PLAY_LED") (class "Default")
      (node (ref "P9") (pin "2") (pinfunction "PLAY_LED_2") (pintype "passive"))
      (node (ref "U3") (pin "82") (pinfunction "P4[28]/RX_MCLK/MAT2[0]/TXD3_82") (pintype "passive"))
    )
    (net (code "47") (name "/POT SCI") (class "Default")
      (node (ref "P9") (pin "22") (pinfunction "POT_SCI_22") (pintype "passive"))
      (node (ref "U3") (pin "47") (pinfunction "P0[1]/TD1/RXD3/SCL1_47") (pintype "passive"))
    )
    (net (code "48") (name "/POT SDA") (class "Default")
      (node (ref "P9") (pin "23") (pinfunction "POT_SDA_23") (pintype "passive"))
      (node (ref "U3") (pin "46") (pinfunction "P0[0]/RD1/TXD3/SDA1_46") (pintype "passive"))
    )
    (net (code "49") (name "/PWM0") (class "Default")
      (node (ref "P3") (pin "54") (pinfunction "PWM0_54") (pintype "passive"))
      (node (ref "U3") (pin "69") (pinfunction "P2[4]/PWM1[5]/DSR1/TRACEDATA1_69") (pintype "passive"))
    )
    (net (code "50") (name "/PWM1") (class "Default")
      (node (ref "P3") (pin "53") (pinfunction "PWM1_53") (pintype "passive"))
      (node (ref "U3") (pin "68") (pinfunction "P2{5}/PWM1[6]/DTR1/TRACEDATA[0]_68") (pintype "passive"))
    )
    (net (code "51") (name "/RESET") (class "Default")
      (node (ref "P9") (pin "16") (pinfunction "RESET*_16") (pintype "passive"))
      (node (ref "R21") (pin "1") (pinfunction "1_1") (pintype "passive"))
      (node (ref "S1") (pin "2") (pinfunction "2_2") (pintype "passive"))
      (node (ref "U3") (pin "17") (pinfunction "~RESET_17") (pintype "passive"))
    )
    (net (code "52") (name "/RSTOUT") (class "Default")
      (node (ref "J4") (pin "1") (pinfunction "1_1") (pintype "passive"))
      (node (ref "U2") (pin "15") (pinfunction "NRST_15") (pintype "passive"))
      (node (ref "U3") (pin "14") (pinfunction "RSTOUT_14") (pintype "passive"))
    )
    (net (code "53") (name "/RX+") (class "Default")
      (node (ref "C13") (pin "1") (pinfunction "1_1") (pintype "passive"))
      (node (ref "P10") (pin "3") (pinfunction "RD+_3") (pintype "passive"))
      (node (ref "R3") (pin "1") (pinfunction "1_1") (pintype "passive"))
      (node (ref "U2") (pin "23") (pinfunction "RX+_23") (pintype "passive"))
    )
    (net (code "54") (name "/RX-") (class "Default")
      (node (ref "C14") (pin "1") (pinfunction "1_1") (pintype "passive"))
      (node (ref "P10") (pin "6") (pinfunction "RD-_6") (pintype "passive"))
      (node (ref "R4") (pin "1") (pinfunction "1_1") (pintype "passive"))
      (node (ref "U2") (pin "22") (pinfunction "RX-_22") (pintype "passive"))
    )
    (net (code "55") (name "/RX0") (class "Default")
      (node (ref "P8") (pin "1") (pinfunction "1_1") (pintype "passive"))
      (node (ref "U3") (pin "99") (pinfunction "P0[3]/RXD0/AD0[6]_99") (pintype "passive"))
    )
    (net (code "56") (name "/SCK1") (class "Default")
      (node (ref "P9") (pin "8") (pinfunction "SCK1_8") (pintype "passive"))
      (node (ref "U3") (pin "62") (pinfunction "P0[15]/TXD1/SCK0/SCK_62") (pintype "passive"))
    )
    (net (code "57") (name "/SD CD") (class "Default")
      (node (ref "P3") (pin "46") (pinfunction "SD_CD_46") (pintype "passive"))
      (node (ref "U3") (pin "52") (pinfunction "P2[11]/EINT1/12STX_CLK_52") (pintype "passive"))
    )
    (net (code "58") (name "/SD CS") (class "Default")
      (node (ref "P2") (pin "2") (pinfunction "CS_2") (pintype "passive"))
      (node (ref "R17") (pin "1") (pinfunction "1_1") (pintype "passive"))
      (node (ref "U3") (pin "79") (pinfunction "P0[6]/12SRX_SDA/SSEL1/MAT2[1]_79") (pintype "passive"))
    )
    (net (code "59") (name "/SD IRQ") (class "Default")
      (node (ref "P9") (pin "4") (pinfunction "SD_IRQ_4") (pintype "passive"))
      (node (ref "U3") (pin "27") (pinfunction "P3[25]/MAT0[0]/PWM1[2]_27") (pintype "passive"))
    )
    (net (code "60") (name "/SD MISO") (class "Default")
      (node (ref "P2") (pin "7") (pinfunction "D0_7") (pintype "passive"))
      (node (ref "R15") (pin "1") (pinfunction "1_1") (pintype "passive"))
      (node (ref "U3") (pin "77") (pinfunction "P0[8]/12STX_WS?MIS01/MAT2[1]_77") (pintype "passive"))
    )
    (net (code "61") (name "/SD MOSI") (class "Default")
      (node (ref "P2") (pin "3") (pinfunction "DI_3") (pintype "passive"))
      (node (ref "R16") (pin "1") (pinfunction "1_1") (pintype "passive"))
      (node (ref "U3") (pin "76") (pinfunction "P0[9]/12STX_SDA/MOSI1/MAT2[3]_76") (pintype "passive"))
    )
    (net (code "62") (name "/SD SCK") (class "Default")
      (node (ref "P2") (pin "5") (pinfunction "SCK_5") (pintype "passive"))
      (node (ref "U3") (pin "78") (pinfunction "P0[7]/12STX_CLK/SCK1/MAT2[1]_78") (pintype "passive"))
    )
    (net (code "63") (name "/SD WP") (class "Default")
      (node (ref "P9") (pin "3") (pinfunction "SD_WP_3") (pintype "passive"))
      (node (ref "U3") (pin "26") (pinfunction "P3[26]/STCLK/MAT0[1]/PWM1[3]_26") (pintype "passive"))
    )
    (net (code "64") (name "/SSEL1") (class "Default")
      (node (ref "P9") (pin "7") (pinfunction "SSEL1_7") (pintype "passive"))
      (node (ref "U3") (pin "63") (pinfunction "P0[16]/RXD1/SSEL0/SSEL_63") (pintype "passive"))
    )
    (net (code "65") (name "/STP1") (class "Default")
      (node (ref "P3") (pin "30") (pinfunction "X_STP*_30") (pintype "passive"))
      (node (ref "U3") (pin "75") (pinfunction "P2[0]/PWM1[1]/TXD1_75") (pintype "passive"))
    )
    (net (code "66") (name "/STP2") (class "Default")
      (node (ref "P3") (pin "31") (pinfunction "Y_STP*_31") (pintype "passive"))
      (node (ref "U3") (pin "74") (pinfunction "P2[1]/PWM1{2}/RXD1_74") (pintype "passive"))
    )
    (net (code "67") (name "/STP3") (class "Default")
      (node (ref "P3") (pin "32") (pinfunction "Z_STP*_32") (pintype "passive"))
      (node (ref "U3") (pin "73") (pinfunction "P2[2]/PWM1[3]/CTS1/TRACEDATA[3]_73") (pintype "passive"))
    )
    (net (code "68") (name "/STP4") (class "Default")
      (node (ref "P3") (pin "29") (pinfunction "STP4_29") (pintype "passive"))
      (node (ref "U3") (pin "70") (pinfunction "P2[3]/PWM1[4]/DCD1/TRACEDATA2[2]_70") (pintype "passive"))
    )
    (net (code "69") (name "/STP5") (class "Default")
      (node (ref "P3") (pin "47") (pinfunction "STP_5_47") (pintype "passive"))
      (node (ref "U3") (pin "65") (pinfunction "P2[8]/TD2/TXD2_65") (pintype "passive"))
    )
    (net (code "70") (name "/TH1") (class "Default")
      (node (ref "P9") (pin "27") (pinfunction "TH1_27") (pintype "passive"))
      (node (ref "U3") (pin "9") (pinfunction "P0[23]/AD0[0]/12SRX_CLK/CAP3[0]_9") (pintype "passive"))
    )
    (net (code "71") (name "/TH2") (class "Default")
      (node (ref "P9") (pin "26") (pinfunction "TH2_26") (pintype "passive"))
      (node (ref "U3") (pin "8") (pinfunction "P0[24]/AD0[1]/12SRX_WS/CAP3[1]_8") (pintype "passive"))
    )
    (net (code "72") (name "/TH3") (class "Default")
      (node (ref "P9") (pin "25") (pinfunction "TH3_25") (pintype "passive"))
      (node (ref "U3") (pin "7") (pinfunction "P0[25]/AD0[2]/12SRX_SDATXD3_7") (pintype "passive"))
    )
    (net (code "73") (name "/TH4") (class "Default")
      (node (ref "P9") (pin "24") (pinfunction "TH4_24") (pintype "passive"))
      (node (ref "U3") (pin "6") (pinfunction "P0[26]AD0[3]/AOUT/RXD3_6") (pintype "passive"))
    )
    (net (code "74") (name "/TX+") (class "Default")
      (node (ref "C11") (pin "1") (pinfunction "1_1") (pintype "passive"))
      (node (ref "P10") (pin "1") (pinfunction "TD+_1") (pintype "passive"))
      (node (ref "R1") (pin "1") (pinfunction "1_1") (pintype "passive"))
      (node (ref "U2") (pin "21") (pinfunction "TX+_21") (pintype "passive"))
    )
    (net (code "75") (name "/TX-") (class "Default")
      (node (ref "C12") (pin "1") (pinfunction "1_1") (pintype "passive"))
      (node (ref "P10") (pin "2") (pinfunction "TD-_2") (pintype "passive"))
      (node (ref "R2") (pin "1") (pinfunction "1_1") (pintype "passive"))
      (node (ref "U2") (pin "20") (pinfunction "TX-_20") (pintype "passive"))
    )
    (net (code "76") (name "/TX0") (class "Default")
      (node (ref "P8") (pin "2") (pinfunction "2_2") (pintype "passive"))
      (node (ref "U3") (pin "98") (pinfunction "P0[2]/TXD0/AD0[7]_98") (pintype "passive"))
    )
    (net (code "77") (name "/USB D+") (class "Default")
      (node (ref "R19") (pin "1") (pinfunction "1_1") (pintype "passive"))
      (node (ref "U3") (pin "29") (pinfunction "P0[29]/USB_D+_29") (pintype "passive"))
    )
    (net (code "78") (name "/USB D-") (class "Default")
      (node (ref "R20") (pin "1") (pinfunction "1_1") (pintype "passive"))
      (node (ref "U3") (pin "30") (pinfunction "P0[30]/USB_D-_30") (pintype "passive"))
    )
    (net (code "79") (name "/USB+") (class "Default")
      (node (ref "C25") (pin "1") (pinfunction "1_1") (pintype "passive"))
      (node (ref "P4") (pin "18") (pinfunction "D+_18") (pintype "passive"))
      (node (ref "P4") (pin "6") (pinfunction "D+_6") (pintype "passive"))
      (node (ref "R18") (pin "2") (pinfunction "2_2") (pintype "passive"))
      (node (ref "R19") (pin "2") (pinfunction "2_2") (pintype "passive"))
    )
    (net (code "80") (name "/USB-") (class "Default")
      (node (ref "C24") (pin "1") (pinfunction "1_1") (pintype "passive"))
      (node (ref "P4") (pin "19") (pinfunction "D-_19") (pintype "passive"))
      (node (ref "P4") (pin "7") (pinfunction "D-_7") (pintype "passive"))
      (node (ref "R20") (pin "2") (pinfunction "2_2") (pintype "passive"))
    )
    (net (code "81") (name "/X MAX") (class "Default")
      (node (ref "P3") (pin "37") (pinfunction "X+_end*_37") (pintype "passive"))
      (node (ref "U3") (pin "39") (pinfunction "PI[25]/MC1A/MAT1[1]_39") (pintype "passive"))
    )
    (net (code "82") (name "/X MIN") (class "Default")
      (node (ref "P3") (pin "40") (pinfunction "X-_end_40") (pintype "passive"))
      (node (ref "U3") (pin "38") (pinfunction "P1[24]/MCFB2/PWM1[5]/MOSI0_38") (pintype "passive"))
    )
    (net (code "83") (name "/Y MAX") (class "Default")
      (node (ref "P3") (pin "38") (pinfunction "Y+_end*_38") (pintype "passive"))
      (node (ref "U3") (pin "43") (pinfunction "P1[27]/CLKOUT/USB_OVTCR/CAP0[1]_43") (pintype "passive"))
    )
    (net (code "84") (name "/Y MIN") (class "Default")
      (node (ref "P3") (pin "41") (pinfunction "Y-_end_41") (pintype "passive"))
      (node (ref "U3") (pin "40") (pinfunction "P1[26]/MC1B/PWM1[6]/CAP0[0]_40") (pintype "passive"))
    )
    (net (code "85") (name "/Z MAX") (class "Default")
      (node (ref "P3") (pin "39") (pinfunction "Z+_end*_39") (pintype "passive"))
      (node (ref "U3") (pin "45") (pinfunction "P1[29]/MC2B/PCAP1[1]/MAT0[1]_45") (pintype "passive"))
    )
    (net (code "86") (name "/Z MIN") (class "Default")
      (node (ref "P3") (pin "43") (pinfunction "Z_-_end_43") (pintype "passive"))
      (node (ref "U3") (pin "44") (pinfunction "P1[28]/MC2A/PCAP1[0]/MAT0[0]_44") (pintype "passive"))
    )
    (net (code "87") (name "/ethsupply") (class "Default")
      (node (ref "C1") (pin "1") (pinfunction "1_1") (pintype "passive"))
      (node (ref "C10") (pin "1") (pinfunction "1_1") (pintype "passive"))
      (node (ref "C2") (pin "1") (pinfunction "1_1") (pintype "passive"))
      (node (ref "C8") (pin "1") (pinfunction "1_1") (pintype "passive"))
      (node (ref "C9") (pin "1") (pinfunction "1_1") (pintype "passive"))
      (node (ref "F1") (pin "2") (pinfunction "13_2") (pintype "passive"))
      (node (ref "P10") (pin "4") (pinfunction "P4_4") (pintype "passive"))
      (node (ref "P10") (pin "5") (pinfunction "P5_5") (pintype "passive"))
      (node (ref "R1") (pin "2") (pinfunction "2_2") (pintype "passive"))
      (node (ref "R2") (pin "2") (pinfunction "2_2") (pintype "passive"))
      (node (ref "R3") (pin "2") (pinfunction "2_2") (pintype "passive"))
      (node (ref "R4") (pin "2") (pinfunction "2_2") (pintype "passive"))
      (node (ref "U2") (pin "1") (pinfunction "VDD2A_1") (pintype "passive"))
      (node (ref "U2") (pin "19") (pinfunction "VDD1A_19") (pintype "passive"))
    )
    (net (code "88") (name "3.3v") (class "Default")
      (node (ref "C17") (pin "2") (pinfunction "2_2") (pintype "passive"))
      (node (ref "C18") (pin "2") (pinfunction "2_2") (pintype "passive"))
      (node (ref "C21") (pin "2") (pinfunction "2_2") (pintype "passive"))
      (node (ref "C27") (pin "2") (pinfunction "2_2") (pintype "passive"))
      (node (ref "C28") (pin "2") (pinfunction "2_2") (pintype "passive"))
      (node (ref "C29") (pin "2") (pinfunction "2_2") (pintype "passive"))
      (node (ref "C30") (pin "2") (pinfunction "2_2") (pintype "passive"))
      (node (ref "C31") (pin "2") (pinfunction "2_2") (pintype "passive"))
      (node (ref "C32") (pin "2") (pinfunction "2_2") (pintype "passive"))
      (node (ref "C4") (pin "1") (pinfunction "1_1") (pintype "passive"))
      (node (ref "C6") (pin "1") (pinfunction "1_1") (pintype "passive"))
      (node (ref "C7") (pin "1") (pinfunction "1_1") (pintype "passive"))
      (node (ref "F1") (pin "1") (pinfunction "14_1") (pintype "passive"))
      (node (ref "L1") (pin "2") (pinfunction "2_2") (pintype "passive"))
      (node (ref "P2") (pin "4") (pinfunction "VCC_4") (pintype "passive"))
      (node (ref "P8") (pin "3") (pinfunction "3_3") (pintype "passive"))
      (node (ref "P9") (pin "15") (pinfunction "3.3v_15") (pintype "passive"))
      (node (ref "P9") (pin "17") (pinfunction "3.3v*_17") (pintype "passive"))
      (node (ref "Q1") (pin "3") (pinfunction "S_3") (pintype "passive"))
      (node (ref "R15") (pin "2") (pinfunction "2_2") (pintype "passive"))
      (node (ref "R16") (pin "2") (pinfunction "2_2") (pintype "passive"))
      (node (ref "R17") (pin "2") (pinfunction "2_2") (pintype "passive"))
      (node (ref "R21") (pin "2") (pinfunction "2_2") (pintype "passive"))
      (node (ref "R22") (pin "2") (pinfunction "2_2") (pintype "passive"))
      (node (ref "R6") (pin "2") (pinfunction "2_2") (pintype "passive"))
      (node (ref "R7") (pin "2") (pinfunction "2_2") (pintype "passive"))
      (node (ref "U1") (pin "5") (pinfunction "vcc_5") (pintype "passive"))
      (node (ref "U2") (pin "9") (pinfunction "VDDIO_9") (pintype "passive"))
      (node (ref "U3") (pin "19") (pinfunction "VBAT_19") (pintype "passive"))
      (node (ref "U3") (pin "28") (pinfunction "VDD[3v3]1_28") (pintype "passive"))
      (node (ref "U3") (pin "42") (pinfunction "VDD[REG][3v3]1_42") (pintype "passive"))
      (node (ref "U3") (pin "54") (pinfunction "VDD[3v3]2_54") (pintype "passive"))
      (node (ref "U3") (pin "71") (pinfunction "VDD[3v3]3_71") (pintype "passive"))
      (node (ref "U3") (pin "84") (pinfunction "VDD[REG][3v3]2_84") (pintype "passive"))
      (node (ref "U3") (pin "96") (pinfunction "VDD[3v3]4_96") (pintype "passive"))
      (node (ref "U4") (pin "3") (pinfunction "OUT_3") (pintype "passive"))
    )
    (net (code "89") (name "5v") (class "Default")
      (node (ref "D1") (pin "1") (pinfunction "A_1") (pintype "passive"))
      (node (ref "J3") (pin "1") (pinfunction "1_1") (pintype "passive"))
      (node (ref "P1") (pin "2") (pinfunction "2_2") (pintype "passive"))
    )
    (net (code "90") (name "AGND") (class "Default")
      (node (ref "C1") (pin "2") (pinfunction "2_2") (pintype "passive"))
      (node (ref "C10") (pin "2") (pinfunction "2_2") (pintype "passive"))
      (node (ref "C11") (pin "2") (pinfunction "2_2") (pintype "passive"))
      (node (ref "C12") (pin "2") (pinfunction "2_2") (pintype "passive"))
      (node (ref "C13") (pin "2") (pinfunction "2_2") (pintype "passive"))
      (node (ref "C14") (pin "2") (pinfunction "2_2") (pintype "passive"))
      (node (ref "C15") (pin "1") (pinfunction "1_1") (pintype "passive"))
      (node (ref "C16") (pin "1") (pinfunction "1_1") (pintype "passive"))
      (node (ref "C17") (pin "1") (pinfunction "1_1") (pintype "passive"))
      (node (ref "C18") (pin "1") (pinfunction "1_1") (pintype "passive"))
      (node (ref "C19") (pin "2") (pinfunction "2_2") (pintype "passive"))
      (node (ref "C2") (pin "2") (pinfunction "2_2") (pintype "passive"))
      (node (ref "C21") (pin "1") (pinfunction "1_1") (pintype "passive"))
      (node (ref "C22") (pin "1") (pinfunction "1_1") (pintype "passive"))
      (node (ref "C23") (pin "1") (pinfunction "1_1") (pintype "passive"))
      (node (ref "C24") (pin "2") (pinfunction "2_2") (pintype "passive"))
      (node (ref "C25") (pin "2") (pinfunction "2_2") (pintype "passive"))
      (node (ref "C26") (pin "2") (pinfunction "2_2") (pintype "passive"))
      (node (ref "C27") (pin "1") (pinfunction "1_1") (pintype "passive"))
      (node (ref "C28") (pin "1") (pinfunction "1_1") (pintype "passive"))
      (node (ref "C29") (pin "1") (pinfunction "1_1") (pintype "passive"))
      (node (ref "C3") (pin "2") (pinfunction "2_2") (pintype "passive"))
      (node (ref "C30") (pin "1") (pinfunction "1_1") (pintype "passive"))
      (node (ref "C31") (pin "1") (pinfunction "1_1") (pintype "passive"))
      (node (ref "C32") (pin "1") (pinfunction "1_1") (pintype "passive"))
      (node (ref "C4") (pin "2") (pinfunction "2_2") (pintype "passive"))
      (node (ref "C5") (pin "2") (pinfunction "2_2") (pintype "passive"))
      (node (ref "C6") (pin "2") (pinfunction "2_2") (pintype "passive"))
      (node (ref "C7") (pin "2") (pinfunction "2_2") (pintype "passive"))
      (node (ref "C8") (pin "2") (pinfunction "2_2") (pintype "passive"))
      (node (ref "C9") (pin "2") (pinfunction "2_2") (pintype "passive"))
      (node (ref "D3") (pin "2") (pinfunction "K_2") (pintype "passive"))
      (node (ref "D4") (pin "2") (pinfunction "K_2") (pintype "passive"))
      (node (ref "D5") (pin "2") (pinfunction "K_2") (pintype "passive"))
      (node (ref "D6") (pin "2") (pinfunction "K_2") (pintype "passive"))
      (node (ref "P1") (pin "1") (pinfunction "1_1") (pintype "passive"))
      (node (ref "P10") (pin "15") (pinfunction "GND_SHEILD0_15") (pintype "passive"))
      (node (ref "P10") (pin "16") (pinfunction "GND_SHEILD1_16") (pintype "passive"))
      (node (ref "P10") (pin "8") (pinfunction "GND_8") (pintype "passive"))
      (node (ref "P2") (pin "10") (pinfunction "10_10") (pintype "passive"))
      (node (ref "P2") (pin "11") (pinfunction "11_11") (pintype "passive"))
      (node (ref "P2") (pin "12") (pinfunction "12_12") (pintype "passive"))
      (node (ref "P2") (pin "13") (pinfunction "13_13") (pintype "passive"))
      (node (ref "P2") (pin "6") (pinfunction "GND_6") (pintype "passive"))
      (node (ref "P2") (pin "9") (pinfunction "9_9") (pintype "passive"))
      (node (ref "P3") (pin "42") (pinfunction "GND*_42") (pintype "passive"))
      (node (ref "P4") (pin "1") (pinfunction "GND_1") (pintype "passive"))
      (node (ref "P4") (pin "12") (pinfunction "GND_12") (pintype "passive"))
      (node (ref "P4") (pin "13") (pinfunction "GND_13") (pintype "passive"))
      (node (ref "P4") (pin "24") (pinfunction "GND_24") (pintype "passive"))
      (node (ref "P8") (pin "6") (pinfunction "6_6") (pintype "passive"))
      (node (ref "P9") (pin "14") (pinfunction "AGND_14") (pintype "passive"))
      (node (ref "P9") (pin "19") (pinfunction "GND*_19") (pintype "passive"))
      (node (ref "P9") (pin "20") (pinfunction "GND*_20") (pintype "passive"))
      (node (ref "R12") (pin "2") (pinfunction "2_2") (pintype "passive"))
      (node (ref "R13") (pin "1") (pinfunction "1_1") (pintype "passive"))
      (node (ref "R14") (pin "1") (pinfunction "1_1") (pintype "passive"))
      (node (ref "R5") (pin "1") (pinfunction "1_1") (pintype "passive"))
      (node (ref "S1") (pin "1") (pinfunction "1_1") (pintype "passive"))
      (node (ref "S2") (pin "1") (pinfunction "1_1") (pintype "passive"))
      (node (ref "U1") (pin "3") (pinfunction "GND_3") (pintype "passive"))
      (node (ref "U2") (pin "25") (pinfunction "GND_25") (pintype "passive"))
      (node (ref "U3") (pin "11") (pinfunction "VSSA_11") (pintype "passive"))
      (node (ref "U3") (pin "15") (pinfunction "VREFN_15") (pintype "passive"))
      (node (ref "U3") (pin "31") (pinfunction "VSS1_31") (pintype "passive"))
      (node (ref "U3") (pin "41") (pinfunction "VSS2_41") (pintype "passive"))
      (node (ref "U3") (pin "55") (pinfunction "VSS3_55") (pintype "passive"))
      (node (ref "U3") (pin "72") (pinfunction "VSS4_72") (pintype "passive"))
      (node (ref "U3") (pin "83") (pinfunction "VSS6_83") (pintype "passive"))
      (node (ref "U3") (pin "97") (pinfunction "VSS5_97") (pintype "passive"))
      (node (ref "U4") (pin "2") (pinfunction "GND_2") (pintype "passive"))
    )
    (net (code "91") (name "Net-(D3-A)") (class "Default")
      (node (ref "D3") (pin "1") (pinfunction "A_1") (pintype "passive"))
      (node (ref "R23") (pin "2") (pinfunction "2_2") (pintype "passive"))
    )
    (net (code "92") (name "Net-(D4-A)") (class "Default")
      (node (ref "D4") (pin "1") (pinfunction "A_1") (pintype "passive"))
      (node (ref "R24") (pin "2") (pinfunction "2_2") (pintype "passive"))
    )
    (net (code "93") (name "Net-(D5-A)") (class "Default")
      (node (ref "D5") (pin "1") (pinfunction "A_1") (pintype "passive"))
      (node (ref "R25") (pin "2") (pinfunction "2_2") (pintype "passive"))
    )
    (net (code "94") (name "Net-(D6-A)") (class "Default")
      (node (ref "D6") (pin "1") (pinfunction "A_1") (pintype "passive"))
      (node (ref "R26") (pin "2") (pinfunction "2_2") (pintype "passive"))
    )
    (net (code "95") (name "Net-(P10-Pad10)") (class "Default")
      (node (ref "P10") (pin "10") (pinfunction "10_10") (pintype "passive"))
      (node (ref "R13") (pin "2") (pinfunction "2_2") (pintype "passive"))
    )
    (net (code "96") (name "Net-(P10-Pad11)") (class "Default")
      (node (ref "P10") (pin "11") (pinfunction "11_11") (pintype "passive"))
      (node (ref "R5") (pin "2") (pinfunction "2_2") (pintype "passive"))
    )
    (net (code "97") (name "Net-(Q1-D)") (class "Default")
      (node (ref "Q1") (pin "1") (pinfunction "D_1") (pintype "passive"))
      (node (ref "R18") (pin "1") (pinfunction "1_1") (pintype "passive"))
    )
    (net (code "98") (name "Net-(Q1-G)") (class "Default")
      (node (ref "Q1") (pin "2") (pinfunction "G_2") (pintype "passive"))
      (node (ref "R28") (pin "2") (pinfunction "2_2") (pintype "passive"))
    )
    (net (code "99") (name "Net-(U1-A)") (class "Default")
      (node (ref "J2") (pin "1") (pinfunction "1_1") (pintype "passive"))
      (node (ref "U1") (pin "2") (pinfunction "A_2") (pintype "passive"))
      (node (ref "U2") (pin "14") (pinfunction "NINT/REFCLK0_14") (pintype "passive"))
    )
    (net (code "100") (name "Net-(U1-y)") (class "Default")
      (node (ref "R8") (pin "1") (pinfunction "1_1") (pintype "passive"))
      (node (ref "U1") (pin "4") (pinfunction "y_4") (pintype "passive"))
    )
    (net (code "101") (name "Net-(U2-CRS_DV)") (class "Default")
      (node (ref "R11") (pin "1") (pinfunction "1_1") (pintype "passive"))
      (node (ref "U2") (pin "11") (pinfunction "CRS_DV_11") (pintype "passive"))
    )
    (net (code "102") (name "Net-(U2-RBIAS)") (class "Default")
      (node (ref "R14") (pin "2") (pinfunction "2_2") (pintype "passive"))
      (node (ref "U2") (pin "24") (pinfunction "RBIAS_24") (pintype "passive"))
    )
    (net (code "103") (name "Net-(U2-RXD0)") (class "Default")
      (node (ref "R9") (pin "1") (pinfunction "1_1") (pintype "passive"))
      (node (ref "U2") (pin "8") (pinfunction "RXD0_8") (pintype "passive"))
    )
    (net (code "104") (name "Net-(U2-RXD1)") (class "Default")
      (node (ref "R10") (pin "1") (pinfunction "1_1") (pintype "passive"))
      (node (ref "U2") (pin "7") (pinfunction "RXD1_7") (pintype "passive"))
    )
    (net (code "105") (name "Net-(U2-VDDCR)") (class "Default")
      (node (ref "C3") (pin "1") (pinfunction "1_1") (pintype "passive"))
      (node (ref "C5") (pin "1") (pinfunction "1_1") (pintype "passive"))
      (node (ref "J1") (pin "1") (pinfunction "1_1") (pintype "passive"))
      (node (ref "U2") (pin "6") (pinfunction "VDDCR_6") (pintype "passive"))
    )
    (net (code "106") (name "Net-(U2-XTAL1)") (class "Default")
      (node (ref "C15") (pin "2") (pinfunction "2_2") (pintype "passive"))
      (node (ref "R27") (pin "2") (pinfunction "2_2") (pintype "passive"))
      (node (ref "U2") (pin "5") (pinfunction "XTAL1_5") (pintype "passive"))
      (node (ref "Y1") (pin "1") (pinfunction "OSC1_1") (pintype "passive"))
    )
    (net (code "107") (name "Net-(U2-XTAL2)") (class "Default")
      (node (ref "C16") (pin "2") (pinfunction "2_2") (pintype "passive"))
      (node (ref "R27") (pin "1") (pinfunction "1_1") (pintype "passive"))
      (node (ref "U2") (pin "4") (pinfunction "XTAL2_4") (pintype "passive"))
      (node (ref "Y1") (pin "2") (pinfunction "OSC2_2") (pintype "passive"))
    )
    (net (code "108") (name "Net-(U3-XTAL1)") (class "Default")
      (node (ref "C22") (pin "2") (pinfunction "2_2") (pintype "passive"))
      (node (ref "U3") (pin "22") (pinfunction "XTAL1_22") (pintype "passive"))
      (node (ref "Y2") (pin "2") (pinfunction "OSC2_2") (pintype "passive"))
    )
    (net (code "109") (name "Net-(U3-XTAL2)") (class "Default")
      (node (ref "C23") (pin "2") (pinfunction "2_2") (pintype "passive"))
      (node (ref "U3") (pin "23") (pinfunction "XTAL2_23") (pintype "passive"))
      (node (ref "Y2") (pin "1") (pinfunction "OSC1_1") (pintype "passive"))
    )
    (net (code "110") (name "unconnected-(P2-NC-Pad1)") (class "Default")
      (node (ref "P2") (pin "1") (pinfunction "NC_1") (pintype "passive+no_connect"))
    )
    (net (code "111") (name "unconnected-(P2-RSV-Pad8)") (class "Default")
      (node (ref "P2") (pin "8") (pinfunction "RSV_8") (pintype "passive+no_connect"))
    )
    (net (code "112") (name "unconnected-(P3-EN*-Pad36)") (class "Default")
      (node (ref "P3") (pin "36") (pinfunction "EN*_36") (pintype "passive"))
    )
    (net (code "113") (name "unconnected-(P4-CC1-Pad5)") (class "Default")
      (node (ref "P4") (pin "5") (pinfunction "CC1_5") (pintype "passive+no_connect"))
    )
    (net (code "114") (name "unconnected-(P4-CC2-Pad17)") (class "Default")
      (node (ref "P4") (pin "17") (pinfunction "CC2_17") (pintype "passive+no_connect"))
    )
    (net (code "115") (name "unconnected-(P4-RX1+-Pad23)") (class "Default")
      (node (ref "P4") (pin "23") (pinfunction "RX1+_23") (pintype "passive+no_connect"))
    )
    (net (code "116") (name "unconnected-(P4-RX1--Pad22)") (class "Default")
      (node (ref "P4") (pin "22") (pinfunction "RX1-_22") (pintype "passive+no_connect"))
    )
    (net (code "117") (name "unconnected-(P4-RX2+-Pad11)") (class "Default")
      (node (ref "P4") (pin "11") (pinfunction "RX2+_11") (pintype "passive+no_connect"))
    )
    (net (code "118") (name "unconnected-(P4-RX2--Pad10)") (class "Default")
      (node (ref "P4") (pin "10") (pinfunction "RX2-_10") (pintype "passive+no_connect"))
    )
    (net (code "119") (name "unconnected-(P4-SBU1-Pad8)") (class "Default")
      (node (ref "P4") (pin "8") (pinfunction "SBU1_8") (pintype "passive+no_connect"))
    )
    (net (code "120") (name "unconnected-(P4-SBU2-Pad20)") (class "Default")
      (node (ref "P4") (pin "20") (pinfunction "SBU2_20") (pintype "passive+no_connect"))
    )
    (net (code "121") (name "unconnected-(P4-TX1+-Pad2)") (class "Default")
      (node (ref "P4") (pin "2") (pinfunction "TX1+_2") (pintype "passive+no_connect"))
    )
    (net (code "122") (name "unconnected-(P4-TX1--Pad3)") (class "Default")
      (node (ref "P4") (pin "3") (pinfunction "TX1-_3") (pintype "passive+no_connect"))
    )
    (net (code "123") (name "unconnected-(P4-TX2+-Pad14)") (class "Default")
      (node (ref "P4") (pin "14") (pinfunction "TX2+_14") (pintype "passive+no_connect"))
    )
    (net (code "124") (name "unconnected-(P4-TX2--Pad15)") (class "Default")
      (node (ref "P4") (pin "15") (pinfunction "TX2-_15") (pintype "passive+no_connect"))
    )
    (net (code "125") (name "unconnected-(P10-NC-Pad7)") (class "Default")
      (node (ref "P10") (pin "7") (pinfunction "NC_7") (pintype "passive"))
    )
    (net (code "126") (name "unconnected-(U1-NC-Pad1)") (class "Default")
      (node (ref "U1") (pin "1") (pinfunction "NC_1") (pintype "passive+no_connect"))
    )
    (net (code "127") (name "unconnected-(U3-NC-Pad13)") (class "Default")
      (node (ref "U3") (pin "13") (pinfunction "NC_13") (pintype "passive+no_connect"))
    )
    (net (code "128") (name "unconnected-(U3-P0[27]{slash}SDA0{slash}USB_SDA-Pad25)") (class "Default")
      (node (ref "U3") (pin "25") (pinfunction "P0[27]/SDA0/USB_SDA_25") (pintype "passive"))
    )
    (net (code "129") (name "unconnected-(U3-P0[28]{slash}SCL0{slash}USB_SCL-Pad24)") (class "Default")
      (node (ref "U3") (pin "24") (pinfunction "P0[28]/SCL0/USB_SCL_24") (pintype "passive"))
    )
    (net (code "130") (name "unconnected-(U3-RTCX1-Pad16)") (class "Default")
      (node (ref "U3") (pin "16") (pinfunction "RTCX1_16") (pintype "passive+no_connect"))
    )
    (net (code "131") (name "unconnected-(U3-RTCX2-Pad18)") (class "Default")
      (node (ref "U3") (pin "18") (pinfunction "RTCX2_18") (pintype "passive+no_connect"))
    )
    (net (code "132") (name "v usb") (class "Default")
      (node (ref "D2") (pin "1") (pinfunction "A_1") (pintype "passive"))
      (node (ref "J6") (pin "1") (pinfunction "1_1") (pintype "passive"))
      (node (ref "P4") (pin "16") (pinfunction "VBUS_16") (pintype "passive"))
      (node (ref "P4") (pin "21") (pinfunction "VBUS_21") (pintype "passive"))
      (node (ref "P4") (pin "4") (pinfunction "VBUS_4") (pintype "passive"))
      (node (ref "P4") (pin "9") (pinfunction "VBUS_9") (pintype "passive"))
    )
  )
)
